# I2C_Peripherals.net
KiCad netlist of a schematic drawn in Altium Designer
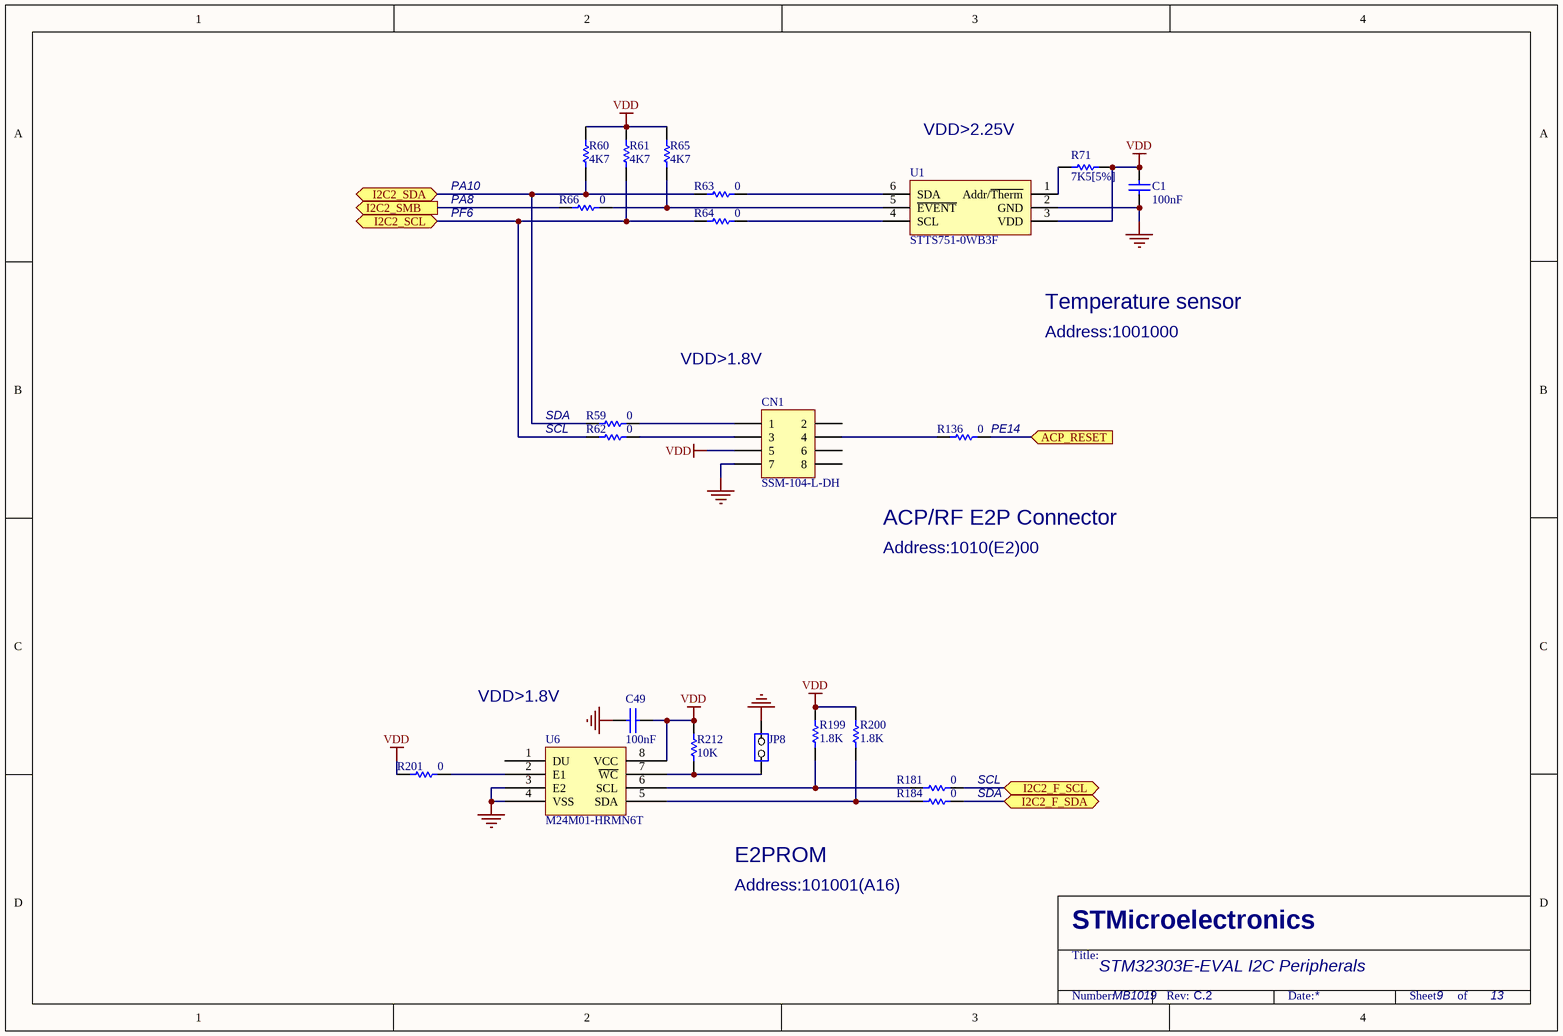
[diagram p0: I2C Peripherals.SCHDOC]

(export (version "E")
  (design (tool "Eeschema 10.0.6"))
  (components
    (comp (ref "C1")
      (value "100nF")
      (footprint "0603C")
      (description "Capacitor")
      (fields (field (name "PUBLISHER") "Altium Limited"))
      (libsource (lib "Miscellaneous Devices") (part "cap"))
    )
    (comp (ref "C49")
      (value "100nF")
      (footprint "0603C")
      (description "Capacitor")
      (libsource (lib "*") (part "CAP"))
    )
    (comp (ref "CN1")
      (value "SSM-104-L-DH")
      (footprint "SSM-104-L-DH")
      (description "Header, 5-Pin, Dual row")
      (fields (field (name "PUBLISHER") "Altium Limited"))
      (libsource (lib "mb1045") (part "SSM-104-L-DH"))
    )
    (comp (ref "JP8") (value "~") (footprint "SIP2") (libsource (lib "*") (part "JP2")))
    (comp (ref "R59")
      (value "0")
      (footprint "0603R")
      (description "Resistor")
      (fields (field (name "PUBLISHER") "Altium Limited"))
      (libsource (lib "Miscellaneous Devices") (part "Res1"))
    )
    (comp (ref "R60")
      (value "4K7")
      (footprint "0603R")
      (description "Resistor")
      (fields (field (name "PUBLISHER") "Altium Limited"))
      (libsource (lib "Miscellaneous Devices") (part "Res1"))
    )
    (comp (ref "R61")
      (value "4K7")
      (footprint "0603R")
      (description "Resistor")
      (fields (field (name "PUBLISHER") "Altium Limited"))
      (libsource (lib "Miscellaneous Devices") (part "Res1"))
    )
    (comp (ref "R62")
      (value "0")
      (footprint "0603R")
      (description "Resistor")
      (fields (field (name "PUBLISHER") "Altium Limited"))
      (libsource (lib "Miscellaneous Devices") (part "Res1"))
    )
    (comp (ref "R63")
      (value "0")
      (footprint "0603R")
      (description "Resistor")
      (fields (field (name "PUBLISHER") "Altium Limited"))
      (libsource (lib "Miscellaneous Devices") (part "Res1"))
    )
    (comp (ref "R64")
      (value "0")
      (footprint "0603R")
      (description "Resistor")
      (fields (field (name "PUBLISHER") "Altium Limited"))
      (libsource (lib "Miscellaneous Devices") (part "Res1"))
    )
    (comp (ref "R65")
      (value "4K7")
      (footprint "0603R")
      (description "Resistor")
      (fields (field (name "PUBLISHER") "Altium Limited"))
      (libsource (lib "Miscellaneous Devices") (part "Res1"))
    )
    (comp (ref "R66")
      (value "0")
      (footprint "0603R")
      (description "Resistor")
      (fields (field (name "PUBLISHER") "Altium Limited"))
      (libsource (lib "Miscellaneous Devices") (part "Res1"))
    )
    (comp (ref "R71")
      (value "7K5[5%]")
      (footprint "0603R")
      (description "Resistor")
      (fields (field (name "PUBLISHER") "Altium Limited"))
      (libsource (lib "Miscellaneous Devices") (part "Res1"))
    )
    (comp (ref "R136")
      (value "0")
      (footprint "0603R")
      (description "Resistor")
      (fields (field (name "PUBLISHER") "Altium Limited"))
      (libsource (lib "Miscellaneous Devices") (part "Res1"))
    )
    (comp (ref "R181")
      (value "0")
      (footprint "0603R")
      (description "Resistor")
      (fields (field (name "PUBLISHER") "Altium Limited"))
      (libsource (lib "Miscellaneous Devices") (part "Res1"))
    )
    (comp (ref "R184")
      (value "0")
      (footprint "0603R")
      (description "Resistor")
      (fields (field (name "PUBLISHER") "Altium Limited"))
      (libsource (lib "Miscellaneous Devices") (part "Res1"))
    )
    (comp (ref "R199")
      (value "1.8K")
      (footprint "0603R")
      (description "Resistor")
      (fields (field (name "PUBLISHER") "Altium Limited"))
      (libsource (lib "Miscellaneous Devices") (part "Res1"))
    )
    (comp (ref "R200")
      (value "1.8K")
      (footprint "0603R")
      (description "Resistor")
      (fields (field (name "PUBLISHER") "Altium Limited"))
      (libsource (lib "Miscellaneous Devices") (part "Res1"))
    )
    (comp (ref "R201")
      (value "0")
      (footprint "0603R")
      (description "Resistor")
      (fields (field (name "PUBLISHER") "Altium Limited"))
      (libsource (lib "Miscellaneous Devices") (part "Res1"))
    )
    (comp (ref "R212")
      (value "10K")
      (footprint "0603R")
      (description "Resistor")
      (fields (field (name "PUBLISHER") "Altium Limited"))
      (libsource (lib "Miscellaneous Devices") (part "res1"))
    )
    (comp (ref "U1")
      (value "STTS751-0WB3F")
      (footprint "SOT23-6L")
      (libsource (lib "MB1019") (part "STTS751-0WB3F"))
    )
    (comp (ref "U6") (value "M24M01-HRMN6T") (footprint "SO8") (libsource (lib "MB988") (part "M24M01")))
  )
  (nets
    (net (code "1") (name "/ACP_RESET") (class "Default")
      (node (ref "R136") (pin "1") (pinfunction "1_1") (pintype "passive"))
    )
    (net (code "2") (name "/I2C2_F_SCL") (class "Default")
      (node (ref "R181") (pin "2") (pinfunction "2_2") (pintype "passive"))
    )
    (net (code "3") (name "/I2C2_F_SDA") (class "Default")
      (node (ref "R184") (pin "2") (pinfunction "2_2") (pintype "passive"))
    )
    (net (code "4") (name "/I2C2_SCL") (class "Default")
      (node (ref "R61") (pin "1") (pinfunction "1_1") (pintype "passive"))
      (node (ref "R62") (pin "1") (pinfunction "1_1") (pintype "passive"))
      (node (ref "R64") (pin "1") (pinfunction "1_1") (pintype "passive"))
    )
    (net (code "5") (name "/I2C2_SDA") (class "Default")
      (node (ref "R59") (pin "1") (pinfunction "1_1") (pintype "passive"))
      (node (ref "R60") (pin "1") (pinfunction "1_1") (pintype "passive"))
      (node (ref "R63") (pin "1") (pinfunction "1_1") (pintype "passive"))
    )
    (net (code "6") (name "/I2C2_SMB") (class "Default")
      (node (ref "R66") (pin "2") (pinfunction "2_2") (pintype "passive"))
    )
    (net (code "7") (name "GND") (class "Default")
      (node (ref "C1") (pin "1") (pinfunction "1_1") (pintype "passive"))
      (node (ref "C49") (pin "1") (pinfunction "1_1") (pintype "passive"))
      (node (ref "CN1") (pin "7") (pinfunction "7_7") (pintype "passive"))
      (node (ref "JP8") (pin "2") (pinfunction "NO_2") (pintype "passive"))
      (node (ref "U1") (pin "2") (pinfunction "GND_2") (pintype "passive"))
      (node (ref "U6") (pin "3") (pinfunction "E2_3") (pintype "passive"))
      (node (ref "U6") (pin "4") (pinfunction "VSS_4") (pintype "passive"))
    )
    (net (code "8") (name "Net-(CN1-Pad1)") (class "Default")
      (node (ref "CN1") (pin "1") (pinfunction "1_1") (pintype "passive"))
      (node (ref "R59") (pin "2") (pinfunction "2_2") (pintype "passive"))
    )
    (net (code "9") (name "Net-(CN1-Pad3)") (class "Default")
      (node (ref "CN1") (pin "3") (pinfunction "3_3") (pintype "passive"))
      (node (ref "R62") (pin "2") (pinfunction "2_2") (pintype "passive"))
    )
    (net (code "10") (name "Net-(CN1-Pad4)") (class "Default")
      (node (ref "CN1") (pin "4") (pinfunction "4_4") (pintype "passive"))
      (node (ref "R136") (pin "2") (pinfunction "2_2") (pintype "passive"))
    )
    (net (code "11") (name "Net-(JP8-COMMON)") (class "Default")
      (node (ref "JP8") (pin "1") (pinfunction "COMMON_1") (pintype "passive"))
      (node (ref "R212") (pin "2") (pinfunction "2_2") (pintype "passive"))
      (node (ref "U6") (pin "7") (pinfunction "~{WC}_7") (pintype "passive"))
    )
    (net (code "12") (name "Net-(U1-Addr{slash}~{Therm})") (class "Default")
      (node (ref "R71") (pin "2") (pinfunction "2_2") (pintype "passive"))
      (node (ref "U1") (pin "1") (pinfunction "Addr/~{Therm}_1") (pintype "passive"))
    )
    (net (code "13") (name "Net-(U1-SCL)") (class "Default")
      (node (ref "R64") (pin "2") (pinfunction "2_2") (pintype "passive"))
      (node (ref "U1") (pin "4") (pinfunction "SCL_4") (pintype "passive"))
    )
    (net (code "14") (name "Net-(U1-SDA)") (class "Default")
      (node (ref "R63") (pin "2") (pinfunction "2_2") (pintype "passive"))
      (node (ref "U1") (pin "6") (pinfunction "SDA_6") (pintype "passive"))
    )
    (net (code "15") (name "Net-(U1-~{EVENT})") (class "Default")
      (node (ref "R65") (pin "1") (pinfunction "1_1") (pintype "passive"))
      (node (ref "R66") (pin "1") (pinfunction "1_1") (pintype "passive"))
      (node (ref "U1") (pin "5") (pinfunction "~{EVENT}_5") (pintype "passive"))
    )
    (net (code "16") (name "Net-(U6-E1)") (class "Default")
      (node (ref "R201") (pin "2") (pinfunction "2_2") (pintype "passive"))
      (node (ref "U6") (pin "2") (pinfunction "E1_2") (pintype "passive"))
    )
    (net (code "17") (name "Net-(U6-SCL)") (class "Default")
      (node (ref "R181") (pin "1") (pinfunction "1_1") (pintype "passive"))
      (node (ref "R199") (pin "1") (pinfunction "1_1") (pintype "passive"))
      (node (ref "U6") (pin "6") (pinfunction "SCL_6") (pintype "passive"))
    )
    (net (code "18") (name "Net-(U6-SDA)") (class "Default")
      (node (ref "R184") (pin "1") (pinfunction "1_1") (pintype "passive"))
      (node (ref "R200") (pin "1") (pinfunction "1_1") (pintype "passive"))
      (node (ref "U6") (pin "5") (pinfunction "SDA_5") (pintype "passive"))
    )
    (net (code "19") (name "VDD") (class "Default")
      (node (ref "C1") (pin "2") (pinfunction "2_2") (pintype "passive"))
      (node (ref "C49") (pin "2") (pinfunction "2_2") (pintype "passive"))
      (node (ref "CN1") (pin "5") (pinfunction "5_5") (pintype "passive"))
      (node (ref "R199") (pin "2") (pinfunction "2_2") (pintype "passive"))
      (node (ref "R200") (pin "2") (pinfunction "2_2") (pintype "passive"))
      (node (ref "R201") (pin "1") (pinfunction "1_1") (pintype "passive"))
      (node (ref "R212") (pin "1") (pinfunction "1_1") (pintype "passive"))
      (node (ref "R60") (pin "2") (pinfunction "2_2") (pintype "passive"))
      (node (ref "R61") (pin "2") (pinfunction "2_2") (pintype "passive"))
      (node (ref "R65") (pin "2") (pinfunction "2_2") (pintype "passive"))
      (node (ref "R71") (pin "1") (pinfunction "1_1") (pintype "passive"))
      (node (ref "U1") (pin "3") (pinfunction "VDD_3") (pintype "passive"))
      (node (ref "U6") (pin "8") (pinfunction "VCC_8") (pintype "passive"))
    )
    (net (code "20") (name "unconnected-(CN1-Pad2)") (class "Default")
      (node (ref "CN1") (pin "2") (pinfunction "2_2") (pintype "passive"))
    )
    (net (code "21") (name "unconnected-(CN1-Pad6)") (class "Default")
      (node (ref "CN1") (pin "6") (pinfunction "6_6") (pintype "passive"))
    )
    (net (code "22") (name "unconnected-(CN1-Pad8)") (class "Default")
      (node (ref "CN1") (pin "8") (pinfunction "8_8") (pintype "passive"))
    )
    (net (code "23") (name "unconnected-(U6-DU-Pad1)") (class "Default")
      (node (ref "U6") (pin "1") (pinfunction "DU_1") (pintype "passive"))
    )
  )
)
